# ccs811.net
KiCad netlist of a schematic drawn in EAGLE
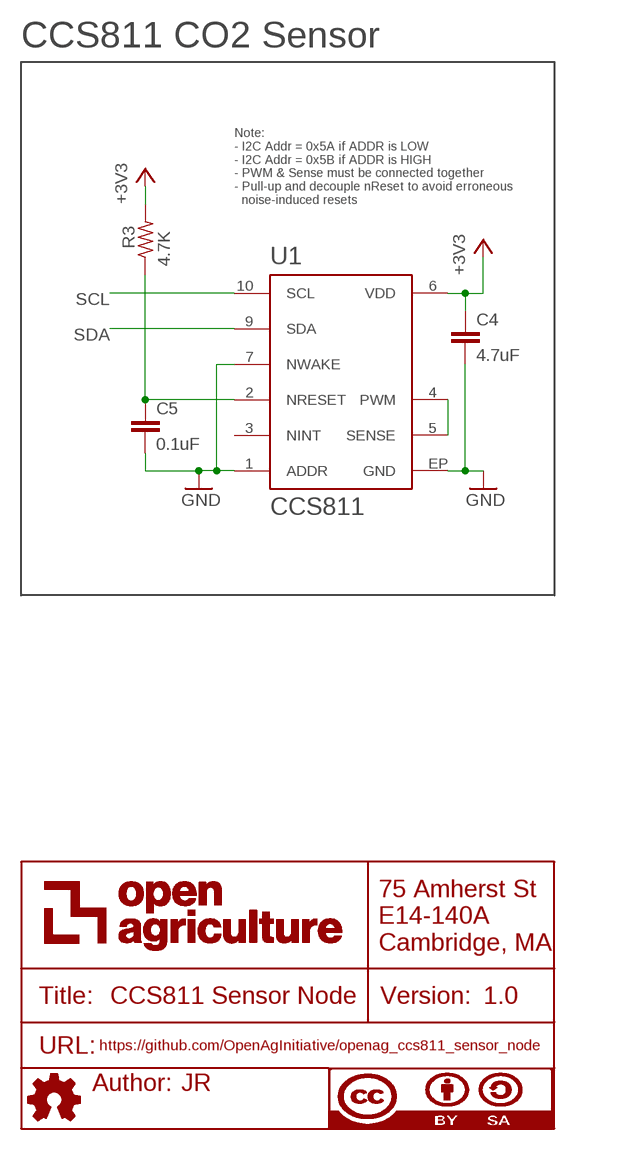
[diagram p0: schematic, sheet 1]

(export (version "E")
  (design (tool "Eeschema 10.0.6"))
  (components
    (comp (ref "C4")
      (value "4.7uF")
      (footprint "eagle-import:C0805")
      (libsource (lib "eagle-import") (part "4.7UF-CL21A475KBQNNNE"))
    )
    (comp (ref "C5")
      (value "0.1uF")
      (footprint "eagle-import:C0603")
      (libsource (lib "eagle-import") (part "0.1UF-C0603C104K5RACTU"))
    )
    (comp (ref "FRAME1")
      (value "DOCFIELD")
      (footprint "eagle-import:DOCFIELD")
      (description "CCS811 CO2 Sensor Node")
      (fields
        (field (name "AUTHOR") "JR")
        (field (name "TITLE") "CCS811 Sensor Node")
        (field (name "URL") "https://github.com/OpenAgInitiative/openag_ccs811_sensor_node")
      )
      (libsource (lib "eagle-import") (part "DOCFIELD"))
    )
    (comp (ref "R3")
      (value "4.7K")
      (footprint "eagle-import:R1206")
      (libsource (lib "eagle-import") (part "4.7K-RC1206JR-074K7L"))
    )
    (comp (ref "U1")
      (value "CCS811")
      (footprint "eagle-import:CCS811")
      (libsource (lib "eagle-import") (part "CCS811"))
    )
  )
  (nets
    (net (code "1") (name "+3V3") (class "Default")
      (node (ref "C4") (pin "1") (pinfunction "1_1") (pintype "passive"))
      (node (ref "R3") (pin "2") (pinfunction "2_2") (pintype "passive"))
      (node (ref "U1") (pin "6") (pinfunction "VDD_6") (pintype "power_in"))
    )
    (net (code "2") (name "GND") (class "Default")
      (node (ref "C4") (pin "2") (pinfunction "2_2") (pintype "passive"))
      (node (ref "C5") (pin "2") (pinfunction "2_2") (pintype "passive"))
      (node (ref "U1") (pin "1") (pinfunction "ADDR_1") (pintype "bidirectional"))
      (node (ref "U1") (pin "7") (pinfunction "NWAKE_7") (pintype "bidirectional"))
      (node (ref "U1") (pin "EP") (pinfunction "GND_EP") (pintype "power_in"))
    )
    (net (code "3") (name "Net-(U1-NRESET)") (class "Default")
      (node (ref "C5") (pin "1") (pinfunction "1_1") (pintype "passive"))
      (node (ref "R3") (pin "1") (pinfunction "1_1") (pintype "passive"))
      (node (ref "U1") (pin "2") (pinfunction "NRESET_2") (pintype "bidirectional"))
    )
    (net (code "4") (name "Net-(U1-PWM)") (class "Default")
      (node (ref "U1") (pin "4") (pinfunction "PWM_4") (pintype "bidirectional"))
      (node (ref "U1") (pin "5") (pinfunction "SENSE_5") (pintype "bidirectional"))
    )
    (net (code "5") (name "SCL") (class "Default")
      (node (ref "U1") (pin "10") (pinfunction "SCL_10") (pintype "bidirectional"))
    )
    (net (code "6") (name "SDA") (class "Default")
      (node (ref "U1") (pin "9") (pinfunction "SDA_9") (pintype "bidirectional"))
    )
    (net (code "7") (name "unconnected-(U1-NINT-Pad3)") (class "Default")
      (node (ref "U1") (pin "3") (pinfunction "NINT_3") (pintype "bidirectional"))
    )
  )
)
